# DE0_Digital_IO_Wing.net
KiCad netlist of a schematic drawn in EAGLE
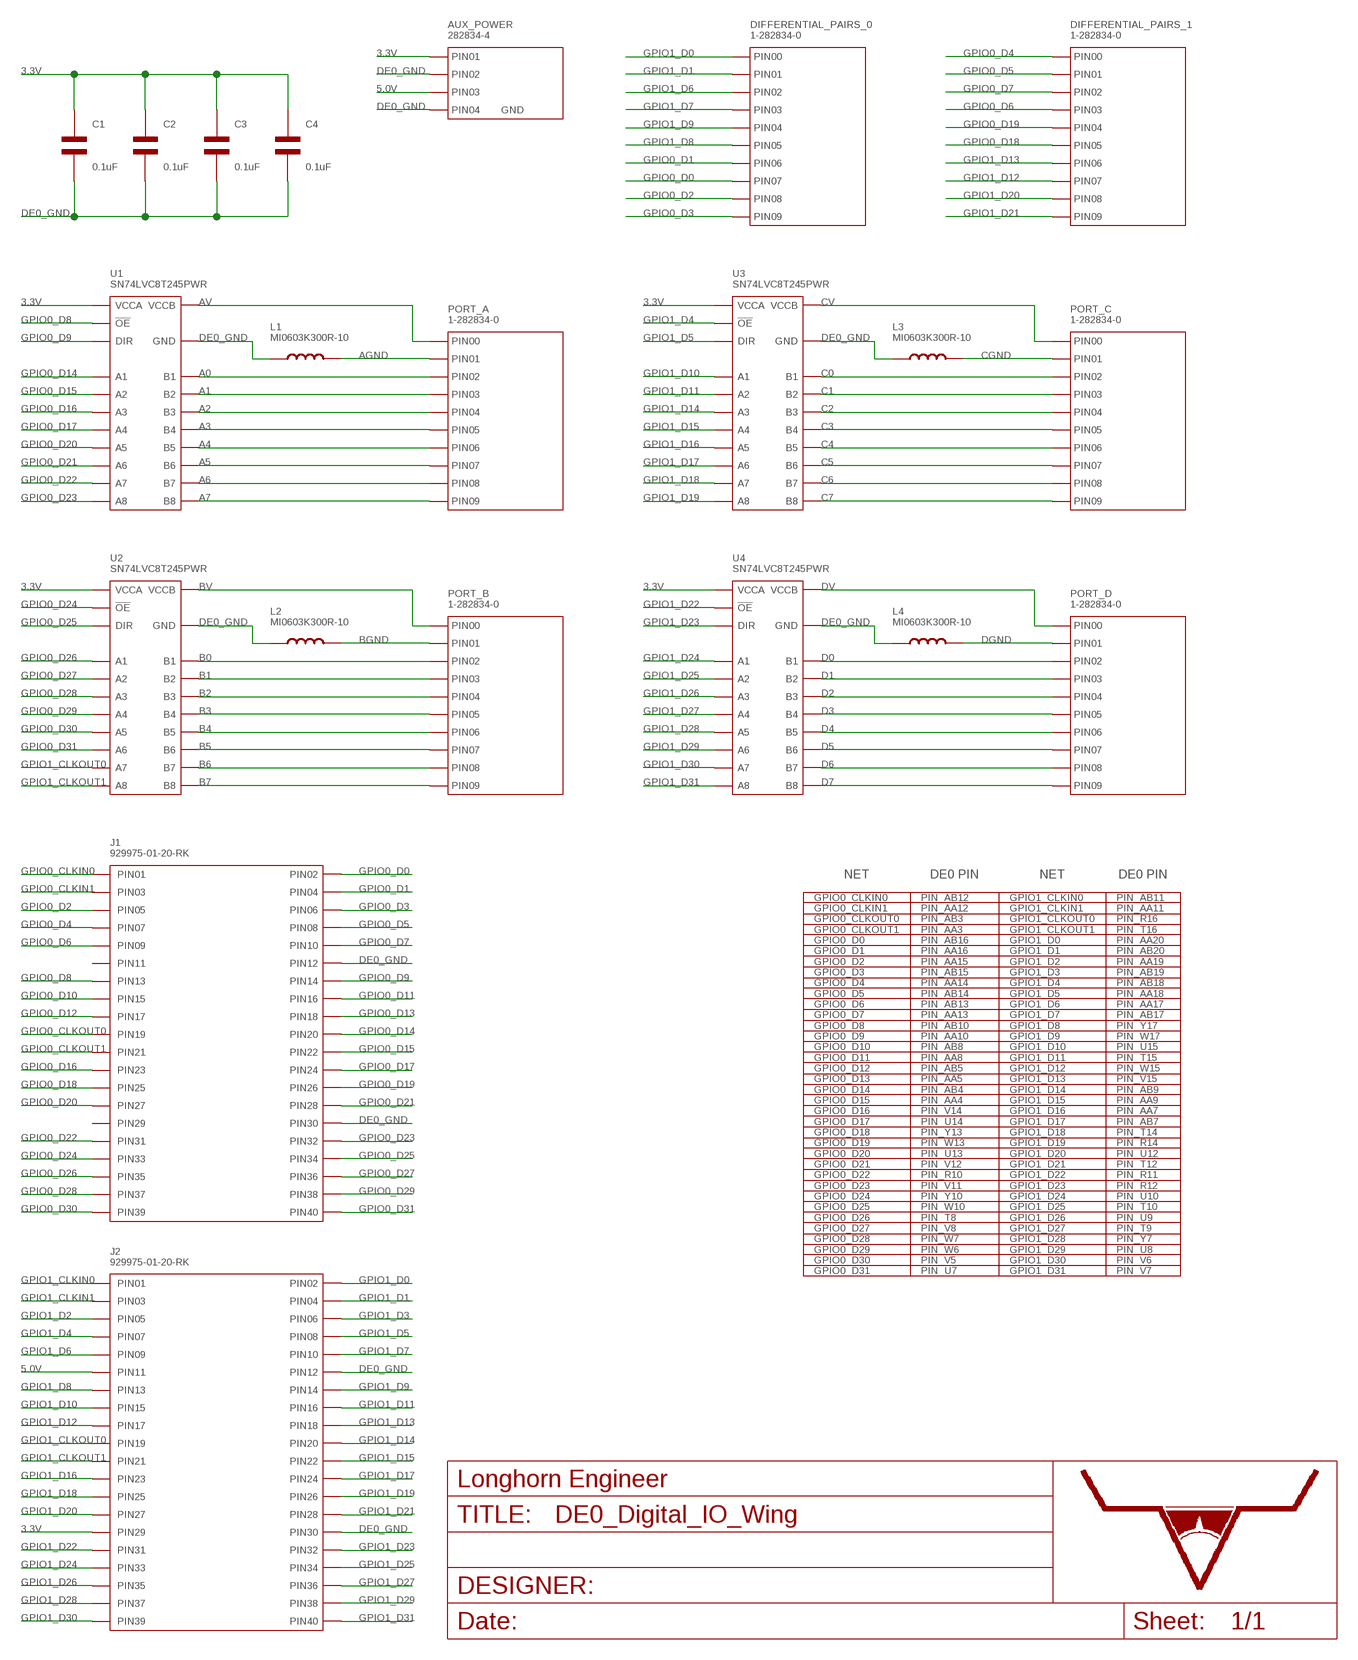
[diagram p0: schematic, sheet 1]

(export (version "E")
  (design (tool "Eeschema 10.0.6"))
  (components
    (comp (ref "AUX_POWER")
      (value "282834-4")
      (footprint "eagle-import:282834-4")
      (fields
        (field (name "LABEL01") "3.3V")
        (field (name "LABEL02") "GND")
        (field (name "LABEL03") "5V")
        (field (name "LABEL04") "GND")
      )
      (libsource (lib "eagle-import") (part "CON_01X04_282834-4"))
    )
    (comp (ref "C1")
      (value "0.1uF")
      (footprint "eagle-import:C0805")
      (libsource (lib "eagle-import") (part "CAPACITOR_NP_0805"))
    )
    (comp (ref "C2")
      (value "0.1uF")
      (footprint "eagle-import:C0805")
      (libsource (lib "eagle-import") (part "CAPACITOR_NP_0805"))
    )
    (comp (ref "C3")
      (value "0.1uF")
      (footprint "eagle-import:C0805")
      (libsource (lib "eagle-import") (part "CAPACITOR_NP_0805"))
    )
    (comp (ref "C4")
      (value "0.1uF")
      (footprint "eagle-import:C0805")
      (libsource (lib "eagle-import") (part "CAPACITOR_NP_0805"))
    )
    (comp (ref "DIFFERENTIAL_PAIRS_0")
      (value "1-282834-0")
      (footprint "eagle-import:1-282834-0")
      (fields
        (field (name "LABEL00") "+ (AA20)")
        (field (name "LABEL01") "- (AB20)")
        (field (name "LABEL02") "+ (AA17)")
        (field (name "LABEL03") "- (AB17)")
        (field (name "LABEL04") "+ (W17)")
        (field (name "LABEL05") "- (Y17)")
        (field (name "LABEL06") "+ (AA16)")
        (field (name "LABEL07") "- (AB16)")
        (field (name "LABEL08") "+ (AA15)")
        (field (name "LABEL09") "- (AB15)")
      )
      (libsource (lib "eagle-import") (part "PH_1X101-282834-0"))
    )
    (comp (ref "DIFFERENTIAL_PAIRS_1")
      (value "1-282834-0")
      (footprint "eagle-import:1-282834-0")
      (fields
        (field (name "LABEL00") "+ (AA14)")
        (field (name "LABEL01") "- (AB14)")
        (field (name "LABEL02") "+ (AA13)")
        (field (name "LABEL03") "- (AB13)")
        (field (name "LABEL04") "+ (W13)")
        (field (name "LABEL05") "- (Y13)")
        (field (name "LABEL06") "+ (V15)")
        (field (name "LABEL07") "- (W15)")
        (field (name "LABEL08") "+ (U12)")
        (field (name "LABEL09") "- (T12)")
      )
      (libsource (lib "eagle-import") (part "PH_1X101-282834-0"))
    )
    (comp (ref "FRAME")
      (value "LHE_FRAME")
      (footprint "eagle-import:LHE_FRAME")
      (fields (field (name "DNAME") "Parker Dillmann") (field (name "REVNUM") "REV: 0"))
      (libsource (lib "eagle-import") (part "LHE_FRAME"))
    )
    (comp (ref "J1")
      (value "929975-01-20-RK")
      (footprint "eagle-import:2.54MM_02X20_PIN_HEADER")
      (libsource (lib "eagle-import") (part "CON_02X202.54MM_PIN_HEADER"))
    )
    (comp (ref "J2")
      (value "929975-01-20-RK")
      (footprint "eagle-import:2.54MM_02X20_PIN_HEADER")
      (libsource (lib "eagle-import") (part "CON_02X202.54MM_PIN_HEADER"))
    )
    (comp (ref "L1")
      (value "MI0603K300R-10")
      (footprint "eagle-import:L0603")
      (libsource (lib "eagle-import") (part "INDUCTOR_0603"))
    )
    (comp (ref "L2")
      (value "MI0603K300R-10")
      (footprint "eagle-import:L0603")
      (libsource (lib "eagle-import") (part "INDUCTOR_0603"))
    )
    (comp (ref "L3")
      (value "MI0603K300R-10")
      (footprint "eagle-import:L0603")
      (libsource (lib "eagle-import") (part "INDUCTOR_0603"))
    )
    (comp (ref "L4")
      (value "MI0603K300R-10")
      (footprint "eagle-import:L0603")
      (libsource (lib "eagle-import") (part "INDUCTOR_0603"))
    )
    (comp (ref "PORT_A")
      (value "1-282834-0")
      (footprint "eagle-import:1-282834-0")
      (fields
        (field (name "LABEL00") "A_VREF")
        (field (name "LABEL01") "A_GND")
        (field (name "LABEL02") "A0 (AB4)")
        (field (name "LABEL03") "A1 (AA4)")
        (field (name "LABEL04") "A2 (V14)")
        (field (name "LABEL05") "A3 (U14)")
        (field (name "LABEL06") "A4 (U13)")
        (field (name "LABEL07") "A5 (V12)")
        (field (name "LABEL08") "A6 (R10)")
        (field (name "LABEL09") "A7 (V11)")
      )
      (libsource (lib "eagle-import") (part "PH_1X101-282834-0"))
    )
    (comp (ref "PORT_B")
      (value "1-282834-0")
      (footprint "eagle-import:1-282834-0")
      (fields
        (field (name "LABEL00") "B_VREF")
        (field (name "LABEL01") "B_GND")
        (field (name "LABEL02") "B0 (T8)")
        (field (name "LABEL03") "B1 (V8)")
        (field (name "LABEL04") "B2 (W7)")
        (field (name "LABEL05") "B3 (W6)")
        (field (name "LABEL06") "B4 (V5)")
        (field (name "LABEL07") "B5 (U7)")
        (field (name "LABEL08") "B6 (AA19)")
        (field (name "LABEL09") "B7 (AB19)")
      )
      (libsource (lib "eagle-import") (part "PH_1X101-282834-0"))
    )
    (comp (ref "PORT_C")
      (value "1-282834-0")
      (footprint "eagle-import:1-282834-0")
      (fields
        (field (name "LABEL00") "C_VREF")
        (field (name "LABEL01") "C_GND")
        (field (name "LABEL02") "C0 (U15)")
        (field (name "LABEL03") "C1 (T15)")
        (field (name "LABEL04") "C2 (AB9)")
        (field (name "LABEL05") "C3 (AA9)")
        (field (name "LABEL06") "C4 (AA7)")
        (field (name "LABEL07") "C5 (AB7)")
        (field (name "LABEL08") "C6 (T14)")
        (field (name "LABEL09") "C7 (R14)")
      )
      (libsource (lib "eagle-import") (part "PH_1X101-282834-0"))
    )
    (comp (ref "PORT_D")
      (value "1-282834-0")
      (footprint "eagle-import:1-282834-0")
      (fields
        (field (name "LABEL00") "D_VREF")
        (field (name "LABEL01") "D_GND")
        (field (name "LABEL02") "D0 (U10)")
        (field (name "LABEL03") "D1 (T10)")
        (field (name "LABEL04") "D2 (U9)")
        (field (name "LABEL05") "D3 (T9)")
        (field (name "LABEL06") "D4 (Y7)")
        (field (name "LABEL07") "D5 (U8)")
        (field (name "LABEL08") "D6 (V6)")
        (field (name "LABEL09") "D7 (V7)")
      )
      (libsource (lib "eagle-import") (part "PH_1X101-282834-0"))
    )
    (comp (ref "U1")
      (value "SN74LVC8T245PWR")
      (footprint "eagle-import:SN74LVC8T245_TTSOP-24")
      (libsource (lib "eagle-import") (part "SN74LVC8T245PWR"))
    )
    (comp (ref "U2")
      (value "SN74LVC8T245PWR")
      (footprint "eagle-import:SN74LVC8T245_TTSOP-24")
      (libsource (lib "eagle-import") (part "SN74LVC8T245PWR"))
    )
    (comp (ref "U3")
      (value "SN74LVC8T245PWR")
      (footprint "eagle-import:SN74LVC8T245_TTSOP-24")
      (libsource (lib "eagle-import") (part "SN74LVC8T245PWR"))
    )
    (comp (ref "U4")
      (value "SN74LVC8T245PWR")
      (footprint "eagle-import:SN74LVC8T245_TTSOP-24")
      (libsource (lib "eagle-import") (part "SN74LVC8T245PWR"))
    )
  )
  (nets
    (net (code "1") (name "/3.3V") (class "Default")
      (node (ref "AUX_POWER") (pin "P$1") (pinfunction "1_P$1") (pintype "passive"))
      (node (ref "C1") (pin "P$1") (pinfunction "P$1_P$1") (pintype "passive"))
      (node (ref "C2") (pin "P$1") (pinfunction "P$1_P$1") (pintype "passive"))
      (node (ref "C3") (pin "P$1") (pinfunction "P$1_P$1") (pintype "passive"))
      (node (ref "C4") (pin "P$1") (pinfunction "P$1_P$1") (pintype "passive"))
      (node (ref "J2") (pin "29") (pinfunction "29_29") (pintype "bidirectional"))
      (node (ref "U1") (pin "P$1") (pinfunction "VCCA_P$1") (pintype "bidirectional"))
      (node (ref "U2") (pin "P$1") (pinfunction "VCCA_P$1") (pintype "bidirectional"))
      (node (ref "U3") (pin "P$1") (pinfunction "VCCA_P$1") (pintype "bidirectional"))
      (node (ref "U4") (pin "P$1") (pinfunction "VCCA_P$1") (pintype "bidirectional"))
    )
    (net (code "2") (name "/5.0V") (class "Default")
      (node (ref "AUX_POWER") (pin "P$3") (pinfunction "3_P$3") (pintype "passive"))
      (node (ref "J2") (pin "11") (pinfunction "11_11") (pintype "bidirectional"))
    )
    (net (code "3") (name "/A0") (class "Default")
      (node (ref "PORT_A") (pin "P$3") (pinfunction "3_P$3") (pintype "bidirectional"))
      (node (ref "U1") (pin "P$21") (pinfunction "B1_P$21") (pintype "bidirectional"))
    )
    (net (code "4") (name "/A1") (class "Default")
      (node (ref "PORT_A") (pin "P$4") (pinfunction "4_P$4") (pintype "bidirectional"))
      (node (ref "U1") (pin "P$20") (pinfunction "B2_P$20") (pintype "bidirectional"))
    )
    (net (code "5") (name "/A2") (class "Default")
      (node (ref "PORT_A") (pin "P$5") (pinfunction "5_P$5") (pintype "bidirectional"))
      (node (ref "U1") (pin "P$19") (pinfunction "B3_P$19") (pintype "bidirectional"))
    )
    (net (code "6") (name "/A3") (class "Default")
      (node (ref "PORT_A") (pin "P$6") (pinfunction "6_P$6") (pintype "bidirectional"))
      (node (ref "U1") (pin "P$18") (pinfunction "B4_P$18") (pintype "bidirectional"))
    )
    (net (code "7") (name "/A4") (class "Default")
      (node (ref "PORT_A") (pin "P$7") (pinfunction "7_P$7") (pintype "bidirectional"))
      (node (ref "U1") (pin "P$17") (pinfunction "B5_P$17") (pintype "bidirectional"))
    )
    (net (code "8") (name "/A5") (class "Default")
      (node (ref "PORT_A") (pin "P$8") (pinfunction "8_P$8") (pintype "bidirectional"))
      (node (ref "U1") (pin "P$16") (pinfunction "B6_P$16") (pintype "bidirectional"))
    )
    (net (code "9") (name "/A6") (class "Default")
      (node (ref "PORT_A") (pin "P$9") (pinfunction "9_P$9") (pintype "bidirectional"))
      (node (ref "U1") (pin "P$15") (pinfunction "B7_P$15") (pintype "bidirectional"))
    )
    (net (code "10") (name "/A7") (class "Default")
      (node (ref "PORT_A") (pin "P$10") (pinfunction "10_P$10") (pintype "bidirectional"))
      (node (ref "U1") (pin "P$14") (pinfunction "B8_P$14") (pintype "bidirectional"))
    )
    (net (code "11") (name "/AGND") (class "Default")
      (node (ref "L1") (pin "P$2") (pinfunction "P$2_P$2") (pintype "passive"))
      (node (ref "PORT_A") (pin "P$2") (pinfunction "2_P$2") (pintype "bidirectional"))
    )
    (net (code "12") (name "/AV") (class "Default")
      (node (ref "PORT_A") (pin "P$1") (pinfunction "1_P$1") (pintype "bidirectional"))
      (node (ref "U1") (pin "P$23") (pinfunction "VCCB_P$23") (pintype "bidirectional"))
      (node (ref "U1") (pin "P$24") (pinfunction "VCCB_P$24") (pintype "bidirectional"))
    )
    (net (code "13") (name "/B0") (class "Default")
      (node (ref "PORT_B") (pin "P$3") (pinfunction "3_P$3") (pintype "bidirectional"))
      (node (ref "U2") (pin "P$21") (pinfunction "B1_P$21") (pintype "bidirectional"))
    )
    (net (code "14") (name "/B1") (class "Default")
      (node (ref "PORT_B") (pin "P$4") (pinfunction "4_P$4") (pintype "bidirectional"))
      (node (ref "U2") (pin "P$20") (pinfunction "B2_P$20") (pintype "bidirectional"))
    )
    (net (code "15") (name "/B2") (class "Default")
      (node (ref "PORT_B") (pin "P$5") (pinfunction "5_P$5") (pintype "bidirectional"))
      (node (ref "U2") (pin "P$19") (pinfunction "B3_P$19") (pintype "bidirectional"))
    )
    (net (code "16") (name "/B3") (class "Default")
      (node (ref "PORT_B") (pin "P$6") (pinfunction "6_P$6") (pintype "bidirectional"))
      (node (ref "U2") (pin "P$18") (pinfunction "B4_P$18") (pintype "bidirectional"))
    )
    (net (code "17") (name "/B4") (class "Default")
      (node (ref "PORT_B") (pin "P$7") (pinfunction "7_P$7") (pintype "bidirectional"))
      (node (ref "U2") (pin "P$17") (pinfunction "B5_P$17") (pintype "bidirectional"))
    )
    (net (code "18") (name "/B5") (class "Default")
      (node (ref "PORT_B") (pin "P$8") (pinfunction "8_P$8") (pintype "bidirectional"))
      (node (ref "U2") (pin "P$16") (pinfunction "B6_P$16") (pintype "bidirectional"))
    )
    (net (code "19") (name "/B6") (class "Default")
      (node (ref "PORT_B") (pin "P$9") (pinfunction "9_P$9") (pintype "bidirectional"))
      (node (ref "U2") (pin "P$15") (pinfunction "B7_P$15") (pintype "bidirectional"))
    )
    (net (code "20") (name "/B7") (class "Default")
      (node (ref "PORT_B") (pin "P$10") (pinfunction "10_P$10") (pintype "bidirectional"))
      (node (ref "U2") (pin "P$14") (pinfunction "B8_P$14") (pintype "bidirectional"))
    )
    (net (code "21") (name "/BGND") (class "Default")
      (node (ref "L2") (pin "P$2") (pinfunction "P$2_P$2") (pintype "passive"))
      (node (ref "PORT_B") (pin "P$2") (pinfunction "2_P$2") (pintype "bidirectional"))
    )
    (net (code "22") (name "/BV") (class "Default")
      (node (ref "PORT_B") (pin "P$1") (pinfunction "1_P$1") (pintype "bidirectional"))
      (node (ref "U2") (pin "P$23") (pinfunction "VCCB_P$23") (pintype "bidirectional"))
      (node (ref "U2") (pin "P$24") (pinfunction "VCCB_P$24") (pintype "bidirectional"))
    )
    (net (code "23") (name "/C0") (class "Default")
      (node (ref "PORT_C") (pin "P$3") (pinfunction "3_P$3") (pintype "bidirectional"))
      (node (ref "U3") (pin "P$21") (pinfunction "B1_P$21") (pintype "bidirectional"))
    )
    (net (code "24") (name "/C1") (class "Default")
      (node (ref "PORT_C") (pin "P$4") (pinfunction "4_P$4") (pintype "bidirectional"))
      (node (ref "U3") (pin "P$20") (pinfunction "B2_P$20") (pintype "bidirectional"))
    )
    (net (code "25") (name "/C2") (class "Default")
      (node (ref "PORT_C") (pin "P$5") (pinfunction "5_P$5") (pintype "bidirectional"))
      (node (ref "U3") (pin "P$19") (pinfunction "B3_P$19") (pintype "bidirectional"))
    )
    (net (code "26") (name "/C3") (class "Default")
      (node (ref "PORT_C") (pin "P$6") (pinfunction "6_P$6") (pintype "bidirectional"))
      (node (ref "U3") (pin "P$18") (pinfunction "B4_P$18") (pintype "bidirectional"))
    )
    (net (code "27") (name "/C4") (class "Default")
      (node (ref "PORT_C") (pin "P$7") (pinfunction "7_P$7") (pintype "bidirectional"))
      (node (ref "U3") (pin "P$17") (pinfunction "B5_P$17") (pintype "bidirectional"))
    )
    (net (code "28") (name "/C5") (class "Default")
      (node (ref "PORT_C") (pin "P$8") (pinfunction "8_P$8") (pintype "bidirectional"))
      (node (ref "U3") (pin "P$16") (pinfunction "B6_P$16") (pintype "bidirectional"))
    )
    (net (code "29") (name "/C6") (class "Default")
      (node (ref "PORT_C") (pin "P$9") (pinfunction "9_P$9") (pintype "bidirectional"))
      (node (ref "U3") (pin "P$15") (pinfunction "B7_P$15") (pintype "bidirectional"))
    )
    (net (code "30") (name "/C7") (class "Default")
      (node (ref "PORT_C") (pin "P$10") (pinfunction "10_P$10") (pintype "bidirectional"))
      (node (ref "U3") (pin "P$14") (pinfunction "B8_P$14") (pintype "bidirectional"))
    )
    (net (code "31") (name "/CGND") (class "Default")
      (node (ref "L3") (pin "P$2") (pinfunction "P$2_P$2") (pintype "passive"))
      (node (ref "PORT_C") (pin "P$2") (pinfunction "2_P$2") (pintype "bidirectional"))
    )
    (net (code "32") (name "/CV") (class "Default")
      (node (ref "PORT_C") (pin "P$1") (pinfunction "1_P$1") (pintype "bidirectional"))
      (node (ref "U3") (pin "P$23") (pinfunction "VCCB_P$23") (pintype "bidirectional"))
      (node (ref "U3") (pin "P$24") (pinfunction "VCCB_P$24") (pintype "bidirectional"))
    )
    (net (code "33") (name "/D0") (class "Default")
      (node (ref "PORT_D") (pin "P$3") (pinfunction "3_P$3") (pintype "bidirectional"))
      (node (ref "U4") (pin "P$21") (pinfunction "B1_P$21") (pintype "bidirectional"))
    )
    (net (code "34") (name "/D1") (class "Default")
      (node (ref "PORT_D") (pin "P$4") (pinfunction "4_P$4") (pintype "bidirectional"))
      (node (ref "U4") (pin "P$20") (pinfunction "B2_P$20") (pintype "bidirectional"))
    )
    (net (code "35") (name "/D2") (class "Default")
      (node (ref "PORT_D") (pin "P$5") (pinfunction "5_P$5") (pintype "bidirectional"))
      (node (ref "U4") (pin "P$19") (pinfunction "B3_P$19") (pintype "bidirectional"))
    )
    (net (code "36") (name "/D3") (class "Default")
      (node (ref "PORT_D") (pin "P$6") (pinfunction "6_P$6") (pintype "bidirectional"))
      (node (ref "U4") (pin "P$18") (pinfunction "B4_P$18") (pintype "bidirectional"))
    )
    (net (code "37") (name "/D4") (class "Default")
      (node (ref "PORT_D") (pin "P$7") (pinfunction "7_P$7") (pintype "bidirectional"))
      (node (ref "U4") (pin "P$17") (pinfunction "B5_P$17") (pintype "bidirectional"))
    )
    (net (code "38") (name "/D5") (class "Default")
      (node (ref "PORT_D") (pin "P$8") (pinfunction "8_P$8") (pintype "bidirectional"))
      (node (ref "U4") (pin "P$16") (pinfunction "B6_P$16") (pintype "bidirectional"))
    )
    (net (code "39") (name "/D6") (class "Default")
      (node (ref "PORT_D") (pin "P$9") (pinfunction "9_P$9") (pintype "bidirectional"))
      (node (ref "U4") (pin "P$15") (pinfunction "B7_P$15") (pintype "bidirectional"))
    )
    (net (code "40") (name "/D7") (class "Default")
      (node (ref "PORT_D") (pin "P$10") (pinfunction "10_P$10") (pintype "bidirectional"))
      (node (ref "U4") (pin "P$14") (pinfunction "B8_P$14") (pintype "bidirectional"))
    )
    (net (code "41") (name "/DE0_GND") (class "Default")
      (node (ref "AUX_POWER") (pin "P$2") (pinfunction "2_P$2") (pintype "passive"))
      (node (ref "AUX_POWER") (pin "P$4") (pinfunction "4_P$4") (pintype "passive"))
      (node (ref "C1") (pin "P$2") (pinfunction "P$2_P$2") (pintype "passive"))
      (node (ref "C2") (pin "P$2") (pinfunction "P$2_P$2") (pintype "passive"))
      (node (ref "C3") (pin "P$2") (pinfunction "P$2_P$2") (pintype "passive"))
      (node (ref "C4") (pin "P$2") (pinfunction "P$2_P$2") (pintype "passive"))
      (node (ref "J1") (pin "12") (pinfunction "12_12") (pintype "bidirectional"))
      (node (ref "J1") (pin "30") (pinfunction "30_30") (pintype "bidirectional"))
      (node (ref "J2") (pin "12") (pinfunction "12_12") (pintype "bidirectional"))
      (node (ref "J2") (pin "30") (pinfunction "30_30") (pintype "bidirectional"))
      (node (ref "L1") (pin "P$1") (pinfunction "P$1_P$1") (pintype "passive"))
      (node (ref "L2") (pin "P$1") (pinfunction "P$1_P$1") (pintype "passive"))
      (node (ref "L3") (pin "P$1") (pinfunction "P$1_P$1") (pintype "passive"))
      (node (ref "L4") (pin "P$1") (pinfunction "P$1_P$1") (pintype "passive"))
      (node (ref "U1") (pin "P$11") (pinfunction "GND_P$11") (pintype "bidirectional"))
      (node (ref "U1") (pin "P$12") (pinfunction "GND_P$12") (pintype "bidirectional"))
      (node (ref "U1") (pin "P$13") (pinfunction "GND_P$13") (pintype "bidirectional"))
      (node (ref "U2") (pin "P$11") (pinfunction "GND_P$11") (pintype "bidirectional"))
      (node (ref "U2") (pin "P$12") (pinfunction "GND_P$12") (pintype "bidirectional"))
      (node (ref "U2") (pin "P$13") (pinfunction "GND_P$13") (pintype "bidirectional"))
      (node (ref "U3") (pin "P$11") (pinfunction "GND_P$11") (pintype "bidirectional"))
      (node (ref "U3") (pin "P$12") (pinfunction "GND_P$12") (pintype "bidirectional"))
      (node (ref "U3") (pin "P$13") (pinfunction "GND_P$13") (pintype "bidirectional"))
      (node (ref "U4") (pin "P$11") (pinfunction "GND_P$11") (pintype "bidirectional"))
      (node (ref "U4") (pin "P$12") (pinfunction "GND_P$12") (pintype "bidirectional"))
      (node (ref "U4") (pin "P$13") (pinfunction "GND_P$13") (pintype "bidirectional"))
    )
    (net (code "42") (name "/DGND") (class "Default")
      (node (ref "L4") (pin "P$2") (pinfunction "P$2_P$2") (pintype "passive"))
      (node (ref "PORT_D") (pin "P$2") (pinfunction "2_P$2") (pintype "bidirectional"))
    )
    (net (code "43") (name "/DV") (class "Default")
      (node (ref "PORT_D") (pin "P$1") (pinfunction "1_P$1") (pintype "bidirectional"))
      (node (ref "U4") (pin "P$23") (pinfunction "VCCB_P$23") (pintype "bidirectional"))
      (node (ref "U4") (pin "P$24") (pinfunction "VCCB_P$24") (pintype "bidirectional"))
    )
    (net (code "44") (name "/GPIO0_CLKIN0") (class "Default")
      (node (ref "J1") (pin "1") (pinfunction "1_1") (pintype "bidirectional"))
    )
    (net (code "45") (name "/GPIO0_CLKIN1") (class "Default")
      (node (ref "J1") (pin "3") (pinfunction "3_3") (pintype "bidirectional"))
    )
    (net (code "46") (name "/GPIO0_CLKOUT0") (class "Default")
      (node (ref "J1") (pin "19") (pinfunction "19_19") (pintype "bidirectional"))
    )
    (net (code "47") (name "/GPIO0_CLKOUT1") (class "Default")
      (node (ref "J1") (pin "21") (pinfunction "21_21") (pintype "bidirectional"))
    )
    (net (code "48") (name "/GPIO0_D0") (class "Default")
      (node (ref "DIFFERENTIAL_PAIRS_0") (pin "P$8") (pinfunction "8_P$8") (pintype "bidirectional"))
      (node (ref "J1") (pin "2") (pinfunction "2_2") (pintype "bidirectional"))
    )
    (net (code "49") (name "/GPIO0_D1") (class "Default")
      (node (ref "DIFFERENTIAL_PAIRS_0") (pin "P$7") (pinfunction "7_P$7") (pintype "bidirectional"))
      (node (ref "J1") (pin "4") (pinfunction "4_4") (pintype "bidirectional"))
    )
    (net (code "50") (name "/GPIO0_D2") (class "Default")
      (node (ref "DIFFERENTIAL_PAIRS_0") (pin "P$9") (pinfunction "9_P$9") (pintype "bidirectional"))
      (node (ref "J1") (pin "5") (pinfunction "5_5") (pintype "bidirectional"))
    )
    (net (code "51") (name "/GPIO0_D3") (class "Default")
      (node (ref "DIFFERENTIAL_PAIRS_0") (pin "P$10") (pinfunction "10_P$10") (pintype "bidirectional"))
      (node (ref "J1") (pin "6") (pinfunction "6_6") (pintype "bidirectional"))
    )
    (net (code "52") (name "/GPIO0_D4") (class "Default")
      (node (ref "DIFFERENTIAL_PAIRS_1") (pin "P$1") (pinfunction "1_P$1") (pintype "bidirectional"))
      (node (ref "J1") (pin "7") (pinfunction "7_7") (pintype "bidirectional"))
    )
    (net (code "53") (name "/GPIO0_D5") (class "Default")
      (node (ref "DIFFERENTIAL_PAIRS_1") (pin "P$2") (pinfunction "2_P$2") (pintype "bidirectional"))
      (node (ref "J1") (pin "8") (pinfunction "8_8") (pintype "bidirectional"))
    )
    (net (code "54") (name "/GPIO0_D6") (class "Default")
      (node (ref "DIFFERENTIAL_PAIRS_1") (pin "P$4") (pinfunction "4_P$4") (pintype "bidirectional"))
      (node (ref "J1") (pin "9") (pinfunction "9_9") (pintype "bidirectional"))
    )
    (net (code "55") (name "/GPIO0_D7") (class "Default")
      (node (ref "DIFFERENTIAL_PAIRS_1") (pin "P$3") (pinfunction "3_P$3") (pintype "bidirectional"))
      (node (ref "J1") (pin "10") (pinfunction "10_10") (pintype "bidirectional"))
    )
    (net (code "56") (name "/GPIO0_D8") (class "Default")
      (node (ref "J1") (pin "13") (pinfunction "13_13") (pintype "bidirectional"))
      (node (ref "U1") (pin "P$22") (pinfunction "~{OE}_P$22") (pintype "bidirectional"))
    )
    (net (code "57") (name "/GPIO0_D9") (class "Default")
      (node (ref "J1") (pin "14") (pinfunction "14_14") (pintype "bidirectional"))
      (node (ref "U1") (pin "P$2") (pinfunction "DIR_P$2") (pintype "bidirectional"))
    )
    (net (code "58") (name "/GPIO0_D10") (class "Default")
      (node (ref "J1") (pin "15") (pinfunction "15_15") (pintype "bidirectional"))
    )
    (net (code "59") (name "/GPIO0_D11") (class "Default")
      (node (ref "J1") (pin "16") (pinfunction "16_16") (pintype "bidirectional"))
    )
    (net (code "60") (name "/GPIO0_D12") (class "Default")
      (node (ref "J1") (pin "17") (pinfunction "17_17") (pintype "bidirectional"))
    )
    (net (code "61") (name "/GPIO0_D13") (class "Default")
      (node (ref "J1") (pin "18") (pinfunction "18_18") (pintype "bidirectional"))
    )
    (net (code "62") (name "/GPIO0_D14") (class "Default")
      (node (ref "J1") (pin "20") (pinfunction "20_20") (pintype "bidirectional"))
      (node (ref "U1") (pin "P$3") (pinfunction "A1_P$3") (pintype "bidirectional"))
    )
    (net (code "63") (name "/GPIO0_D15") (class "Default")
      (node (ref "J1") (pin "22") (pinfunction "22_22") (pintype "bidirectional"))
      (node (ref "U1") (pin "P$4") (pinfunction "A2_P$4") (pintype "bidirectional"))
    )
    (net (code "64") (name "/GPIO0_D16") (class "Default")
      (node (ref "J1") (pin "23") (pinfunction "23_23") (pintype "bidirectional"))
      (node (ref "U1") (pin "P$5") (pinfunction "A3_P$5") (pintype "bidirectional"))
    )
    (net (code "65") (name "/GPIO0_D17") (class "Default")
      (node (ref "J1") (pin "24") (pinfunction "24_24") (pintype "bidirectional"))
      (node (ref "U1") (pin "P$6") (pinfunction "A4_P$6") (pintype "bidirectional"))
    )
    (net (code "66") (name "/GPIO0_D18") (class "Default")
      (node (ref "DIFFERENTIAL_PAIRS_1") (pin "P$6") (pinfunction "6_P$6") (pintype "bidirectional"))
      (node (ref "J1") (pin "25") (pinfunction "25_25") (pintype "bidirectional"))
    )
    (net (code "67") (name "/GPIO0_D19") (class "Default")
      (node (ref "DIFFERENTIAL_PAIRS_1") (pin "P$5") (pinfunction "5_P$5") (pintype "bidirectional"))
      (node (ref "J1") (pin "26") (pinfunction "26_26") (pintype "bidirectional"))
    )
    (net (code "68") (name "/GPIO0_D20") (class "Default")
      (node (ref "J1") (pin "27") (pinfunction "27_27") (pintype "bidirectional"))
      (node (ref "U1") (pin "P$7") (pinfunction "A5_P$7") (pintype "bidirectional"))
    )
    (net (code "69") (name "/GPIO0_D21") (class "Default")
      (node (ref "J1") (pin "28") (pinfunction "28_28") (pintype "bidirectional"))
      (node (ref "U1") (pin "P$8") (pinfunction "A6_P$8") (pintype "bidirectional"))
    )
    (net (code "70") (name "/GPIO0_D22") (class "Default")
      (node (ref "J1") (pin "31") (pinfunction "31_31") (pintype "bidirectional"))
      (node (ref "U1") (pin "P$9") (pinfunction "A7_P$9") (pintype "bidirectional"))
    )
    (net (code "71") (name "/GPIO0_D23") (class "Default")
      (node (ref "J1") (pin "32") (pinfunction "32_32") (pintype "bidirectional"))
      (node (ref "U1") (pin "P$10") (pinfunction "A8_P$10") (pintype "bidirectional"))
    )
    (net (code "72") (name "/GPIO0_D24") (class "Default")
      (node (ref "J1") (pin "33") (pinfunction "33_33") (pintype "bidirectional"))
      (node (ref "U2") (pin "P$22") (pinfunction "~{OE}_P$22") (pintype "bidirectional"))
    )
    (net (code "73") (name "/GPIO0_D25") (class "Default")
      (node (ref "J1") (pin "34") (pinfunction "34_34") (pintype "bidirectional"))
      (node (ref "U2") (pin "P$2") (pinfunction "DIR_P$2") (pintype "bidirectional"))
    )
    (net (code "74") (name "/GPIO0_D26") (class "Default")
      (node (ref "J1") (pin "35") (pinfunction "35_35") (pintype "bidirectional"))
      (node (ref "U2") (pin "P$3") (pinfunction "A1_P$3") (pintype "bidirectional"))
    )
    (net (code "75") (name "/GPIO0_D27") (class "Default")
      (node (ref "J1") (pin "36") (pinfunction "36_36") (pintype "bidirectional"))
      (node (ref "U2") (pin "P$4") (pinfunction "A2_P$4") (pintype "bidirectional"))
    )
    (net (code "76") (name "/GPIO0_D28") (class "Default")
      (node (ref "J1") (pin "37") (pinfunction "37_37") (pintype "bidirectional"))
      (node (ref "U2") (pin "P$5") (pinfunction "A3_P$5") (pintype "bidirectional"))
    )
    (net (code "77") (name "/GPIO0_D29") (class "Default")
      (node (ref "J1") (pin "38") (pinfunction "38_38") (pintype "bidirectional"))
      (node (ref "U2") (pin "P$6") (pinfunction "A4_P$6") (pintype "bidirectional"))
    )
    (net (code "78") (name "/GPIO0_D30") (class "Default")
      (node (ref "J1") (pin "39") (pinfunction "39_39") (pintype "bidirectional"))
      (node (ref "U2") (pin "P$7") (pinfunction "A5_P$7") (pintype "bidirectional"))
    )
    (net (code "79") (name "/GPIO0_D31") (class "Default")
      (node (ref "J1") (pin "40") (pinfunction "40_40") (pintype "bidirectional"))
      (node (ref "U2") (pin "P$8") (pinfunction "A6_P$8") (pintype "bidirectional"))
    )
    (net (code "80") (name "/GPIO1_CLKIN0") (class "Default")
      (node (ref "J2") (pin "1") (pinfunction "1_1") (pintype "bidirectional"))
    )
    (net (code "81") (name "/GPIO1_CLKIN1") (class "Default")
      (node (ref "J2") (pin "3") (pinfunction "3_3") (pintype "bidirectional"))
    )
    (net (code "82") (name "/GPIO1_CLKOUT0") (class "Default")
      (node (ref "J2") (pin "19") (pinfunction "19_19") (pintype "bidirectional"))
      (node (ref "U2") (pin "P$9") (pinfunction "A7_P$9") (pintype "bidirectional"))
    )
    (net (code "83") (name "/GPIO1_CLKOUT1") (class "Default")
      (node (ref "J2") (pin "21") (pinfunction "21_21") (pintype "bidirectional"))
      (node (ref "U2") (pin "P$10") (pinfunction "A8_P$10") (pintype "bidirectional"))
    )
    (net (code "84") (name "/GPIO1_D0") (class "Default")
      (node (ref "DIFFERENTIAL_PAIRS_0") (pin "P$1") (pinfunction "1_P$1") (pintype "bidirectional"))
      (node (ref "J2") (pin "2") (pinfunction "2_2") (pintype "bidirectional"))
    )
    (net (code "85") (name "/GPIO1_D1") (class "Default")
      (node (ref "DIFFERENTIAL_PAIRS_0") (pin "P$2") (pinfunction "2_P$2") (pintype "bidirectional"))
      (node (ref "J2") (pin "4") (pinfunction "4_4") (pintype "bidirectional"))
    )
    (net (code "86") (name "/GPIO1_D2") (class "Default")
      (node (ref "J2") (pin "5") (pinfunction "5_5") (pintype "bidirectional"))
    )
    (net (code "87") (name "/GPIO1_D3") (class "Default")
      (node (ref "J2") (pin "6") (pinfunction "6_6") (pintype "bidirectional"))
    )
    (net (code "88") (name "/GPIO1_D4") (class "Default")
      (node (ref "J2") (pin "7") (pinfunction "7_7") (pintype "bidirectional"))
      (node (ref "U3") (pin "P$22") (pinfunction "~{OE}_P$22") (pintype "bidirectional"))
    )
    (net (code "89") (name "/GPIO1_D5") (class "Default")
      (node (ref "J2") (pin "8") (pinfunction "8_8") (pintype "bidirectional"))
      (node (ref "U3") (pin "P$2") (pinfunction "DIR_P$2") (pintype "bidirectional"))
    )
    (net (code "90") (name "/GPIO1_D6") (class "Default")
      (node (ref "DIFFERENTIAL_PAIRS_0") (pin "P$3") (pinfunction "3_P$3") (pintype "bidirectional"))
      (node (ref "J2") (pin "9") (pinfunction "9_9") (pintype "bidirectional"))
    )
    (net (code "91") (name "/GPIO1_D7") (class "Default")
      (node (ref "DIFFERENTIAL_PAIRS_0") (pin "P$4") (pinfunction "4_P$4") (pintype "bidirectional"))
      (node (ref "J2") (pin "10") (pinfunction "10_10") (pintype "bidirectional"))
    )
    (net (code "92") (name "/GPIO1_D8") (class "Default")
      (node (ref "DIFFERENTIAL_PAIRS_0") (pin "P$6") (pinfunction "6_P$6") (pintype "bidirectional"))
      (node (ref "J2") (pin "13") (pinfunction "13_13") (pintype "bidirectional"))
    )
    (net (code "93") (name "/GPIO1_D9") (class "Default")
      (node (ref "DIFFERENTIAL_PAIRS_0") (pin "P$5") (pinfunction "5_P$5") (pintype "bidirectional"))
      (node (ref "J2") (pin "14") (pinfunction "14_14") (pintype "bidirectional"))
    )
    (net (code "94") (name "/GPIO1_D10") (class "Default")
      (node (ref "J2") (pin "15") (pinfunction "15_15") (pintype "bidirectional"))
      (node (ref "U3") (pin "P$3") (pinfunction "A1_P$3") (pintype "bidirectional"))
    )
    (net (code "95") (name "/GPIO1_D11") (class "Default")
      (node (ref "J2") (pin "16") (pinfunction "16_16") (pintype "bidirectional"))
      (node (ref "U3") (pin "P$4") (pinfunction "A2_P$4") (pintype "bidirectional"))
    )
    (net (code "96") (name "/GPIO1_D12") (class "Default")
      (node (ref "DIFFERENTIAL_PAIRS_1") (pin "P$8") (pinfunction "8_P$8") (pintype "bidirectional"))
      (node (ref "J2") (pin "17") (pinfunction "17_17") (pintype "bidirectional"))
    )
    (net (code "97") (name "/GPIO1_D13") (class "Default")
      (node (ref "DIFFERENTIAL_PAIRS_1") (pin "P$7") (pinfunction "7_P$7") (pintype "bidirectional"))
      (node (ref "J2") (pin "18") (pinfunction "18_18") (pintype "bidirectional"))
    )
    (net (code "98") (name "/GPIO1_D14") (class "Default")
      (node (ref "J2") (pin "20") (pinfunction "20_20") (pintype "bidirectional"))
      (node (ref "U3") (pin "P$5") (pinfunction "A3_P$5") (pintype "bidirectional"))
    )
    (net (code "99") (name "/GPIO1_D15") (class "Default")
      (node (ref "J2") (pin "22") (pinfunction "22_22") (pintype "bidirectional"))
      (node (ref "U3") (pin "P$6") (pinfunction "A4_P$6") (pintype "bidirectional"))
    )
    (net (code "100") (name "/GPIO1_D16") (class "Default")
      (node (ref "J2") (pin "23") (pinfunction "23_23") (pintype "bidirectional"))
      (node (ref "U3") (pin "P$7") (pinfunction "A5_P$7") (pintype "bidirectional"))
    )
    (net (code "101") (name "/GPIO1_D17") (class "Default")
      (node (ref "J2") (pin "24") (pinfunction "24_24") (pintype "bidirectional"))
      (node (ref "U3") (pin "P$8") (pinfunction "A6_P$8") (pintype "bidirectional"))
    )
    (net (code "102") (name "/GPIO1_D18") (class "Default")
      (node (ref "J2") (pin "25") (pinfunction "25_25") (pintype "bidirectional"))
      (node (ref "U3") (pin "P$9") (pinfunction "A7_P$9") (pintype "bidirectional"))
    )
    (net (code "103") (name "/GPIO1_D19") (class "Default")
      (node (ref "J2") (pin "26") (pinfunction "26_26") (pintype "bidirectional"))
      (node (ref "U3") (pin "P$10") (pinfunction "A8_P$10") (pintype "bidirectional"))
    )
    (net (code "104") (name "/GPIO1_D20") (class "Default")
      (node (ref "DIFFERENTIAL_PAIRS_1") (pin "P$9") (pinfunction "9_P$9") (pintype "bidirectional"))
      (node (ref "J2") (pin "27") (pinfunction "27_27") (pintype "bidirectional"))
    )
    (net (code "105") (name "/GPIO1_D21") (class "Default")
      (node (ref "DIFFERENTIAL_PAIRS_1") (pin "P$10") (pinfunction "10_P$10") (pintype "bidirectional"))
      (node (ref "J2") (pin "28") (pinfunction "28_28") (pintype "bidirectional"))
    )
    (net (code "106") (name "/GPIO1_D22") (class "Default")
      (node (ref "J2") (pin "31") (pinfunction "31_31") (pintype "bidirectional"))
      (node (ref "U4") (pin "P$22") (pinfunction "~{OE}_P$22") (pintype "bidirectional"))
    )
    (net (code "107") (name "/GPIO1_D23") (class "Default")
      (node (ref "J2") (pin "32") (pinfunction "32_32") (pintype "bidirectional"))
      (node (ref "U4") (pin "P$2") (pinfunction "DIR_P$2") (pintype "bidirectional"))
    )
    (net (code "108") (name "/GPIO1_D24") (class "Default")
      (node (ref "J2") (pin "33") (pinfunction "33_33") (pintype "bidirectional"))
      (node (ref "U4") (pin "P$3") (pinfunction "A1_P$3") (pintype "bidirectional"))
    )
    (net (code "109") (name "/GPIO1_D25") (class "Default")
      (node (ref "J2") (pin "34") (pinfunction "34_34") (pintype "bidirectional"))
      (node (ref "U4") (pin "P$4") (pinfunction "A2_P$4") (pintype "bidirectional"))
    )
    (net (code "110") (name "/GPIO1_D26") (class "Default")
      (node (ref "J2") (pin "35") (pinfunction "35_35") (pintype "bidirectional"))
      (node (ref "U4") (pin "P$5") (pinfunction "A3_P$5") (pintype "bidirectional"))
    )
    (net (code "111") (name "/GPIO1_D27") (class "Default")
      (node (ref "J2") (pin "36") (pinfunction "36_36") (pintype "bidirectional"))
      (node (ref "U4") (pin "P$6") (pinfunction "A4_P$6") (pintype "bidirectional"))
    )
    (net (code "112") (name "/GPIO1_D28") (class "Default")
      (node (ref "J2") (pin "37") (pinfunction "37_37") (pintype "bidirectional"))
      (node (ref "U4") (pin "P$7") (pinfunction "A5_P$7") (pintype "bidirectional"))
    )
    (net (code "113") (name "/GPIO1_D29") (class "Default")
      (node (ref "J2") (pin "38") (pinfunction "38_38") (pintype "bidirectional"))
      (node (ref "U4") (pin "P$8") (pinfunction "A6_P$8") (pintype "bidirectional"))
    )
    (net (code "114") (name "/GPIO1_D30") (class "Default")
      (node (ref "J2") (pin "39") (pinfunction "39_39") (pintype "bidirectional"))
      (node (ref "U4") (pin "P$9") (pinfunction "A7_P$9") (pintype "bidirectional"))
    )
    (net (code "115") (name "/GPIO1_D31") (class "Default")
      (node (ref "J2") (pin "40") (pinfunction "40_40") (pintype "bidirectional"))
      (node (ref "U4") (pin "P$10") (pinfunction "A8_P$10") (pintype "bidirectional"))
    )
    (net (code "116") (name "unconnected-(J1-Pad11)") (class "Default")
      (node (ref "J1") (pin "11") (pinfunction "11_11") (pintype "bidirectional"))
    )
    (net (code "117") (name "unconnected-(J1-Pad29)") (class "Default")
      (node (ref "J1") (pin "29") (pinfunction "29_29") (pintype "bidirectional"))
    )
  )
)
